# Buck_3_3V_line_07.net
KiCad netlist of a schematic drawn in Altium Designer
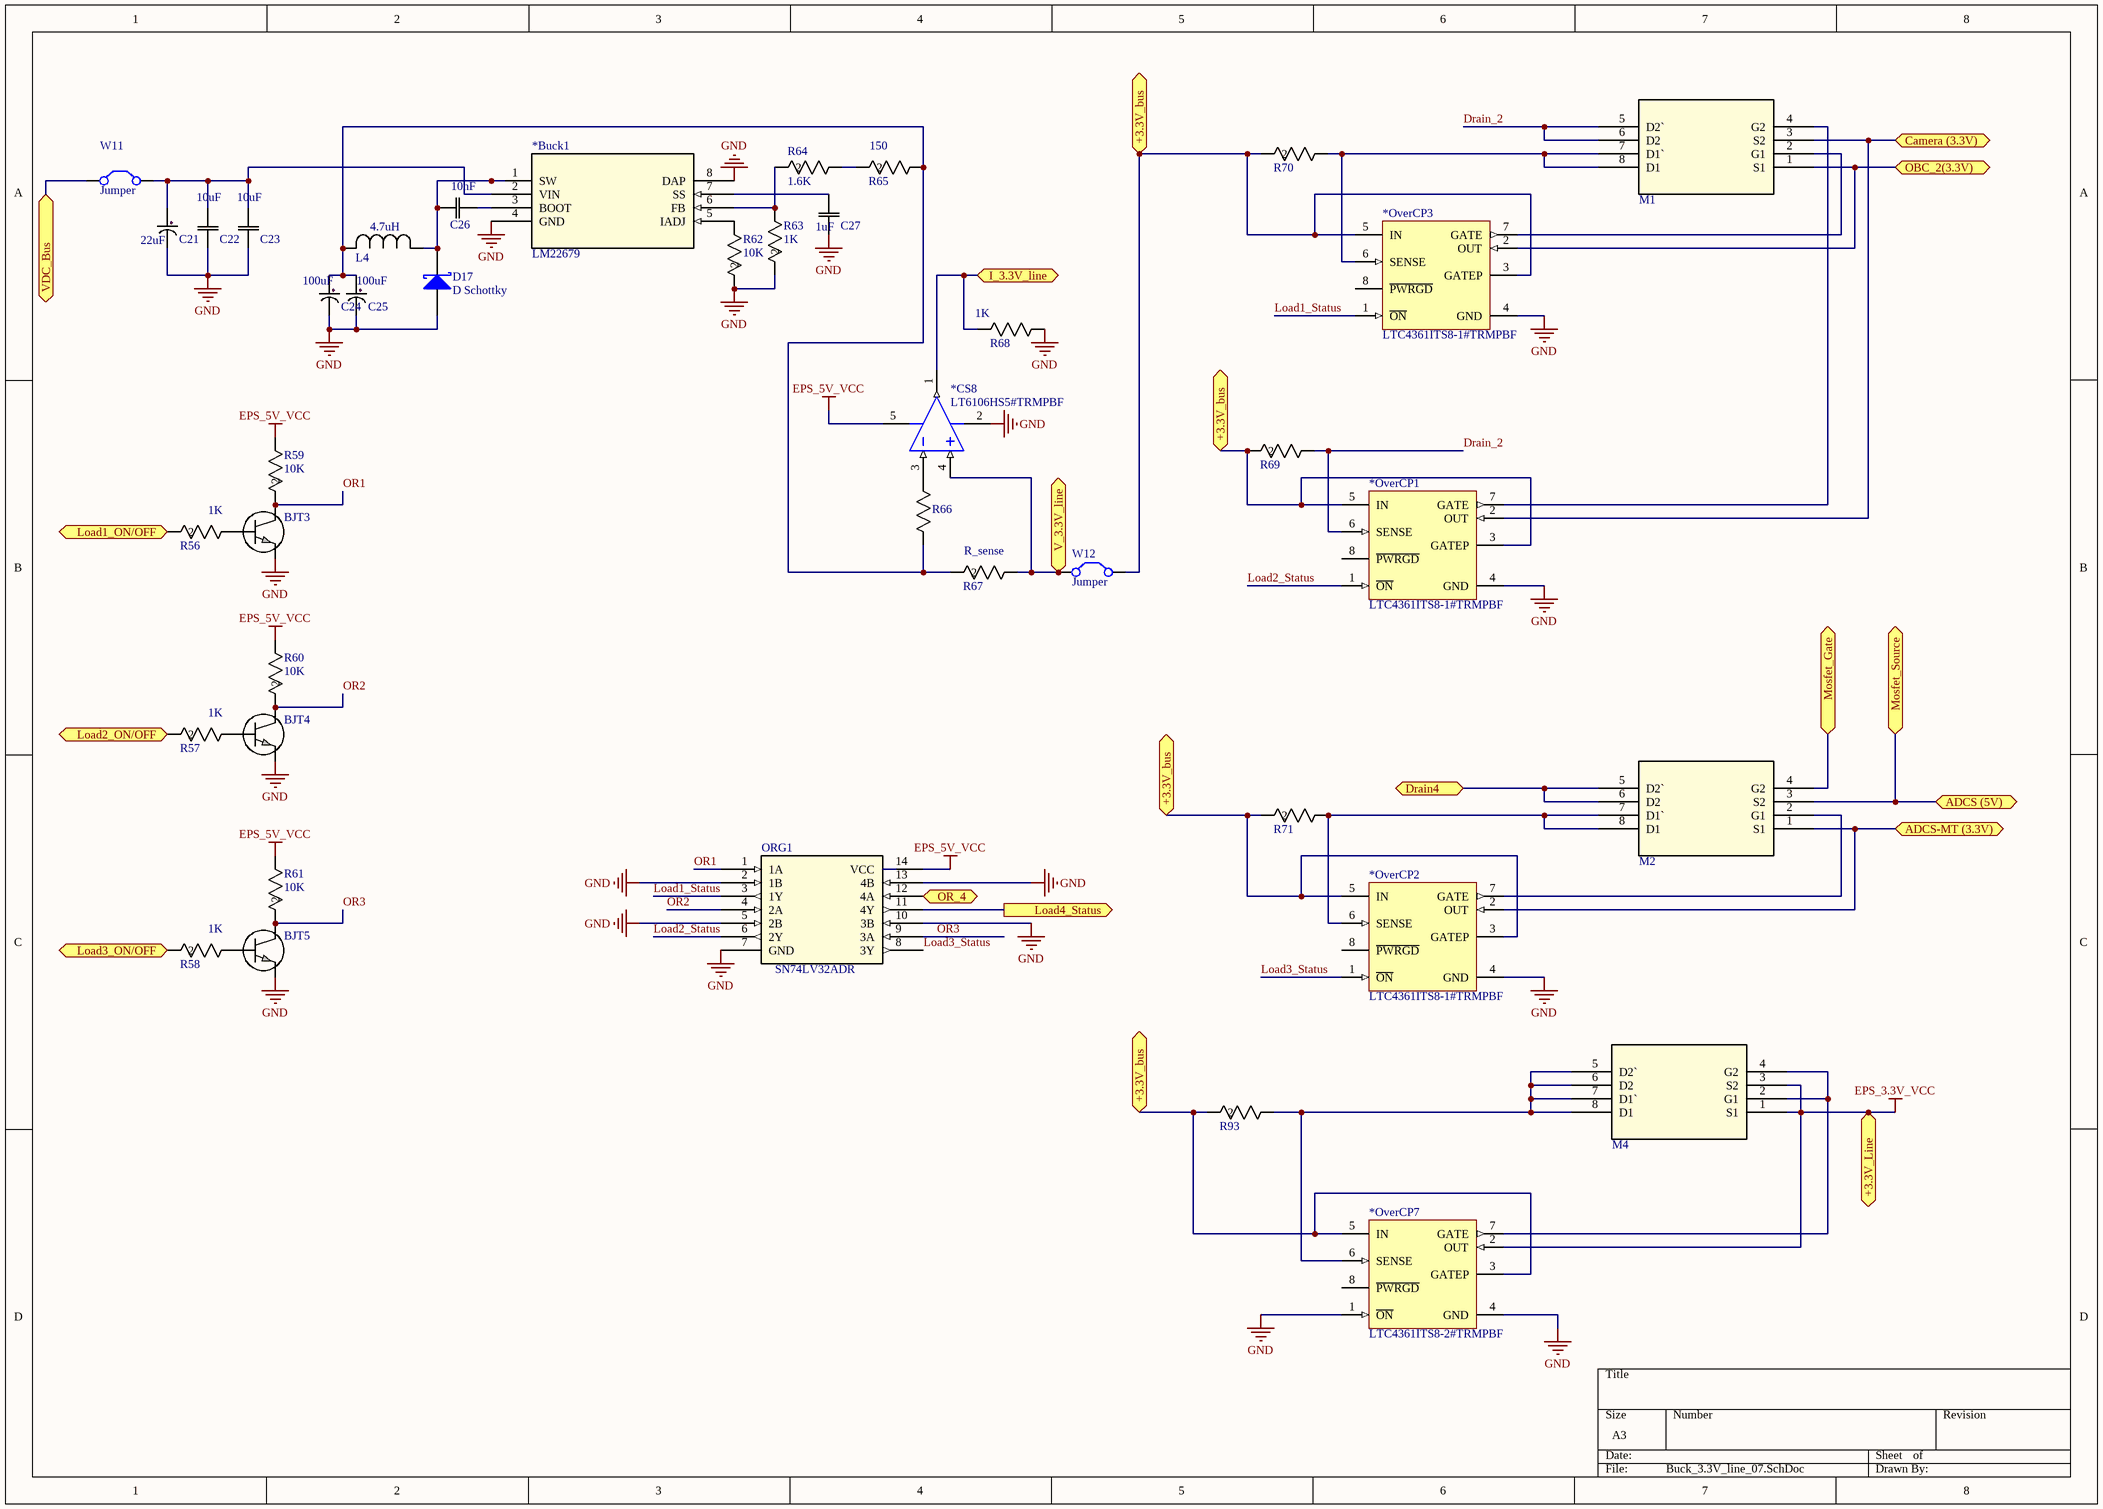
[diagram p0: Buck_3.3V_line_07.SchDoc]

(export (version "E")
  (design (tool "Eeschema 10.0.6"))
  (components
    (comp (ref "*Buck1")
      (value "LM22679")
      (footprint "TJ7A-M")
      (description "step down converter")
      (fields
        (field (name "MANUFACTURER_PART_NUMBER") "lm22679tj-adjnopb")
        (field (name "COPYRIGHT") "Copyright (C) 2015 Accelerated Designs. All rights reserved")
      )
      (libsource (lib "EPS_lib") (part "LM22679"))
    )
    (comp (ref "*CS8")
      (value "LT6106HS5#TRMPBF")
      (footprint "LT-S5-5-TSOT-23_N")
      (fields
        (field (name "LINEAR TECHNOLOGY PART NUMBER") "LT6106")
        (field (name "MANUFACTURER") "Linear Technology")
      )
      (libsource (lib "Linear Technology Operational Amplifiers (LT2000-LT6000)") (part "LT6106HS5#TRMPBF"))
    )
    (comp (ref "*OverCP1")
      (value "LTC4361ITS8-1#TRMPBF")
      (footprint "LT-TS8-8-TSOT-23_V")
      (fields (field (name "MANUFACTURER") "Linear Technology"))
      (libsource (lib "trial05") (part "LTC4361ITS8-1#TRMPBF"))
    )
    (comp (ref "*OverCP2")
      (value "LTC4361ITS8-1#TRMPBF")
      (footprint "LT-TS8-8-TSOT-23_V")
      (fields (field (name "MANUFACTURER") "Linear Technology"))
      (libsource (lib "trial05") (part "LTC4361ITS8-1#TRMPBF"))
    )
    (comp (ref "*OverCP3")
      (value "LTC4361ITS8-1#TRMPBF")
      (footprint "LT-TS8-8-TSOT-23_V")
      (fields (field (name "MANUFACTURER") "Linear Technology"))
      (libsource (lib "trial05") (part "LTC4361ITS8-1#TRMPBF"))
    )
    (comp (ref "*OverCP7")
      (value "LTC4361ITS8-2#TRMPBF")
      (footprint "LT-TS8-8-TSOT-23_V")
      (fields
        (field (name "MANUFACTURER") "Linear Technology")
        (field (name "PARTNUMBER") "LTC4361ITS8-1#TRMPBF")
      )
      (libsource (lib "trial05") (part "LTC4361ITS8-1#TRMPBF"))
    )
    (comp (ref "BJT3")
      (value "MMBT2222A")
      (footprint "SOT-23A_L")
      (description "BJT")
      (fields
        (field (name "MANUFACTURER_PART_NUMBER") "2STF1360")
        (field (name "DIGIKEYPARTNUMBER") "497-5211-2-ND")
        (field (name "COPYRIGHT") "Copyright (C) 2015 Accelerated Designs. All rights reserved")
      )
      (libsource (lib "PCDU_Library") (part "2STF1360"))
    )
    (comp (ref "BJT4")
      (value "MMBT2222A")
      (footprint "SOT-23A_L")
      (description "BJT")
      (fields
        (field (name "MANUFACTURER_PART_NUMBER") "2STF1360")
        (field (name "DIGIKEYPARTNUMBER") "497-5211-2-ND")
        (field (name "COPYRIGHT") "Copyright (C) 2015 Accelerated Designs. All rights reserved")
      )
      (libsource (lib "PCDU_Library") (part "2STF1360"))
    )
    (comp (ref "BJT5")
      (value "MMBT2222A")
      (footprint "SOT-23A_L")
      (description "BJT")
      (fields
        (field (name "MANUFACTURER_PART_NUMBER") "2STF1360")
        (field (name "DIGIKEYPARTNUMBER") "497-5211-2-ND")
        (field (name "COPYRIGHT") "Copyright (C) 2015 Accelerated Designs. All rights reserved")
      )
      (libsource (lib "PCDU_Library") (part "2STF1360"))
    )
    (comp (ref "C21")
      (value "22uF")
      (footprint "TAJB")
      (description "Tantalum Capacitor, 22uF")
      (fields
        (field (name "MANUFACTURER_PART_NUMBER") "TAJB226M010RNJ")
        (field (name "COPYRIGHT") "Copyright (C) 2015 Accelerated Designs. All rights reserved")
      )
      (libsource (lib "PCDU_Library") (part "TAJB226M010RNJ"))
    )
    (comp (ref "C22")
      (value "10uF")
      (footprint "PcbLib1:RC0805N")
      (description "Ceramic Capacitor 10uF")
      (fields
        (field (name "DIGIKEYPARTNUMBER") "399-4925-2-ND")
        (field (name "MANUFACTURER_PART_NUMBER") "C0805C106K8PACTU")
        (field (name "COPYRIGHT") "Copyright (C) 2015 Accelerated Designs. All rights reserved")
      )
      (libsource (lib "PCDU_Library") (part "C0805C106K8PACTU"))
    )
    (comp (ref "C23")
      (value "10uF")
      (footprint "PcbLib1:RC0805N")
      (description "Ceramic Capacitor 10uF")
      (fields
        (field (name "DIGIKEYPARTNUMBER") "399-4925-2-ND")
        (field (name "MANUFACTURER_PART_NUMBER") "C0805C106K8PACTU")
        (field (name "COPYRIGHT") "Copyright (C) 2015 Accelerated Designs. All rights reserved")
      )
      (libsource (lib "PCDU_Library") (part "C0805C106K8PACTU"))
    )
    (comp (ref "C24")
      (value "100uF")
      (footprint "TAJB")
      (description "Tantalum Capacitor. 100uF")
      (fields
        (field (name "MANUFACTURER_PART_NUMBER") "TAJB226M010RNJ")
        (field (name "COPYRIGHT") "Copyright (C) 2015 Accelerated Designs. All rights reserved")
      )
      (libsource (lib "PCDU_Library") (part "TAJB226M010RNJ"))
    )
    (comp (ref "C25")
      (value "100uF")
      (footprint "TAJB")
      (description "Tantalum Capacitor, 100uF")
      (fields
        (field (name "MANUFACTURER_PART_NUMBER") "TAJB226M010RNJ")
        (field (name "COPYRIGHT") "Copyright (C) 2015 Accelerated Designs. All rights reserved")
      )
      (libsource (lib "PCDU_Library") (part "TAJB226M010RNJ"))
    )
    (comp (ref "C26")
      (value "10nF")
      (footprint "RC0805N")
      (description "Ceramic Capacitor 10nF")
      (fields
        (field (name "MANUFACTURER_PART_NUMBER") "GRM155R71H103KA88D")
        (field (name "COPYRIGHT") "Copyright (C) 2015 Accelerated Designs. All rights reserved")
      )
      (libsource (lib "PCDU_Library") (part "GRM155R71H103KA8"))
    )
    (comp (ref "C27")
      (value "1uF")
      (footprint "PcbLib1:RC0805N")
      (description "Ceramic Capacitor 1uF")
      (fields
        (field (name "MANUFACTURER_PART_NUMBER") "GRM188R61C105KA93D")
        (field (name "COPYRIGHT") "Copyright (C) 2015 Accelerated Designs. All rights reserved")
      )
      (libsource (lib "PCDU_Library") (part "GRM188R61C105KA9"))
    )
    (comp (ref "D17")
      (value "D Schottky")
      (footprint "SMB")
      (description "Schottky Diode, 3A")
      (fields (field (name "PUBLISHER") "Altium Limited"))
      (libsource (lib "PCDU_Library") (part "D Schottky"))
    )
    (comp (ref "L4")
      (value "4.7uH")
      (footprint "IND_SPM6530")
      (description "Inductor, 4.7uH")
      (fields
        (field (name "MANUFACTURER_PART_NUMBER") "SPM6530T-4R7M")
        (field (name "COPYRIGHT") "Copyright (C) 2015 Accelerated Designs. All rights reserved")
      )
      (libsource (lib "PCDU_Library") (part "SPM6530T-4R7M"))
    )
    (comp (ref "M1")
      (value "IRF7329TRPBF")
      (footprint "SO8_L")
      (description "P-MOSFET, DUAL PCh -12V 9.2A")
      (fields
        (field (name "MANUFACTURER") "Infineon / IR")
        (field (name "MOUSER PART NO") "942-IRF7329TRPBF")
      )
      (libsource (lib "PCDU_Library") (part "IRF7329TRPBF"))
    )
    (comp (ref "M2")
      (value "IRF7329TRPBF")
      (footprint "SO8_L")
      (description "P-MOSFET, DUAL PCh -12V 9.2A")
      (fields
        (field (name "MANUFACTURER") "Infineon / IR")
        (field (name "MOUSER PART NO") "942-IRF7329TRPBF")
      )
      (libsource (lib "PCDU_Library") (part "IRF7329TRPBF"))
    )
    (comp (ref "M4")
      (value "IRF7329TRPBF")
      (footprint "SO8_L")
      (description "P-MOSFET, DUAL PCh -12V 9.2A")
      (fields
        (field (name "MANUFACTURER") "Infineon / IR")
        (field (name "MOUSER PART NO") "942-IRF7329TRPBF")
      )
      (libsource (lib "PCDU_Library") (part "IRF7329TRPBF"))
    )
    (comp (ref "ORG1")
      (value "SN74LV32ADR")
      (footprint "D14-M")
      (description "OR GATE, 4 Channels")
      (fields
        (field (name "MANUFACTURER") "Texas Instruments")
        (field (name "GENERIC_PART_NUMBER") "SN74LV32A")
        (field (name "COPYRIGHT") "Copyright (C) 2015 Accelerated Designs. All rights reserved")
      )
      (libsource (lib "PCDU_Library") (part "SN74LV32ADR"))
    )
    (comp (ref "R56")
      (value "1K")
      (footprint "RC0805N")
      (description "Thick Film Resistors, 1k ohm")
      (fields
        (field (name "DIGIKEYPARTNUMBER") "311-4.70KCRTR-ND")
        (field (name "MANUFACTURER_PART_NUMBER") "RC0805FR-074K7L")
        (field (name "COPYRIGHT") "Copyright (C) 2015 Accelerated Designs. All rights reserved")
      )
      (libsource (lib "PCDU_Library") (part "RC0805FR"))
    )
    (comp (ref "R57")
      (value "1K")
      (footprint "RC0805N")
      (description "Thick Film Resistors, 1k ohm")
      (fields
        (field (name "DIGIKEYPARTNUMBER") "311-4.70KCRTR-ND")
        (field (name "MANUFACTURER_PART_NUMBER") "RC0805FR-074K7L")
        (field (name "COPYRIGHT") "Copyright (C) 2015 Accelerated Designs. All rights reserved")
      )
      (libsource (lib "PCDU_Library") (part "RC0805FR"))
    )
    (comp (ref "R58")
      (value "1K")
      (footprint "RC0805N")
      (description "Thick Film Resistors, 1k ohm")
      (fields
        (field (name "DIGIKEYPARTNUMBER") "311-4.70KCRTR-ND")
        (field (name "MANUFACTURER_PART_NUMBER") "RC0805FR-074K7L")
        (field (name "COPYRIGHT") "Copyright (C) 2015 Accelerated Designs. All rights reserved")
      )
      (libsource (lib "PCDU_Library") (part "RC0805FR"))
    )
    (comp (ref "R59")
      (value "10K")
      (footprint "PcbLib1:RC0805N")
      (description "Thick Film Resistors, 10k ohm")
      (fields
        (field (name "DIGIKEYPARTNUMBER") "311-4.70KCRTR-ND")
        (field (name "MANUFACTURER_PART_NUMBER") "RC0805FR-074K7L")
        (field (name "COPYRIGHT") "Copyright (C) 2015 Accelerated Designs. All rights reserved")
      )
      (libsource (lib "PCDU_Library") (part "RC0805FR"))
    )
    (comp (ref "R60")
      (value "10K")
      (footprint "PcbLib1:RC0805N")
      (description "Thick Film Resistors, 10k ohm")
      (fields
        (field (name "DIGIKEYPARTNUMBER") "311-4.70KCRTR-ND")
        (field (name "MANUFACTURER_PART_NUMBER") "RC0805FR-074K7L")
        (field (name "COPYRIGHT") "Copyright (C) 2015 Accelerated Designs. All rights reserved")
      )
      (libsource (lib "PCDU_Library") (part "RC0805FR"))
    )
    (comp (ref "R61")
      (value "10K")
      (footprint "PcbLib1:RC0805N")
      (description "Thick Film Resistors, 10k ohm")
      (fields
        (field (name "DIGIKEYPARTNUMBER") "311-4.70KCRTR-ND")
        (field (name "MANUFACTURER_PART_NUMBER") "RC0805FR-074K7L")
        (field (name "COPYRIGHT") "Copyright (C) 2015 Accelerated Designs. All rights reserved")
      )
      (libsource (lib "PCDU_Library") (part "RC0805FR"))
    )
    (comp (ref "R62")
      (value "10K")
      (footprint "RC0805N")
      (description "Thick Film Resistors 10k ohm")
      (fields
        (field (name "DIGIKEYPARTNUMBER") "311-4.70KCRTR-ND")
        (field (name "MANUFACTURER_PART_NUMBER") "RC0805FR-074K7L")
        (field (name "COPYRIGHT") "Copyright (C) 2015 Accelerated Designs. All rights reserved")
      )
      (libsource (lib "PCDU_Library") (part "RC0805FR"))
    )
    (comp (ref "R63")
      (value "1K")
      (footprint "RC0805N")
      (description "Thick Film Resistors, 1k ohm")
      (fields
        (field (name "DIGIKEYPARTNUMBER") "311-4.70KCRTR-ND")
        (field (name "MANUFACTURER_PART_NUMBER") "RC0805FR-074K7L")
        (field (name "COPYRIGHT") "Copyright (C) 2015 Accelerated Designs. All rights reserved")
      )
      (libsource (lib "PCDU_Library") (part "RC0805FR"))
    )
    (comp (ref "R64")
      (value "1.6K")
      (footprint "RC0805N")
      (description "Thick Film Resistors, 1.6kohm")
      (fields
        (field (name "DIGIKEYPARTNUMBER") "311-4.70KCRTR-ND")
        (field (name "MANUFACTURER_PART_NUMBER") "RC0805FR-074K7L")
        (field (name "COPYRIGHT") "Copyright (C) 2015 Accelerated Designs. All rights reserved")
      )
      (libsource (lib "PCDU_Library") (part "RC0805FR"))
    )
    (comp (ref "R65")
      (value "150")
      (footprint "RC0805N")
      (description "Thick Film Resistors, 150 ohm")
      (fields
        (field (name "DIGIKEYPARTNUMBER") "311-4.70KCRTR-ND")
        (field (name "MANUFACTURER_PART_NUMBER") "RC0805FR-074K7L")
        (field (name "COPYRIGHT") "Copyright (C) 2015 Accelerated Designs. All rights reserved")
      )
      (libsource (lib "PCDU_Library") (part "RC0805FR"))
    )
    (comp (ref "R66")
      (value "1K")
      (footprint "RC0805N")
      (description "Thick Film Resistors 0805")
      (fields
        (field (name "DIGIKEYPARTNUMBER") "311-4.70KCRTR-ND")
        (field (name "MANUFACTURER_PART_NUMBER") "RC0805FR-074K7L")
        (field (name "COPYRIGHT") "Copyright (C) 2015 Accelerated Designs. All rights reserved")
      )
      (libsource (lib "Schlib1") (part "RC0805FR"))
    )
    (comp (ref "R67")
      (value "R_sense")
      (footprint "RC0805N")
      (description "Sense Resistor 100m ohm 0805")
      (fields
        (field (name "DIGIKEYPARTNUMBER") "311-.10STR-ND")
        (field (name "MANUFACTURER_PART_NUMBER") "RL0805FR-070R1L")
        (field (name "COPYRIGHT") "Copyright (C) 2015 Accelerated Designs. All rights reserved")
      )
      (libsource (lib "Schlib1") (part "RL0805FR-070R1L"))
    )
    (comp (ref "R68")
      (value "1K")
      (footprint "RC0805N")
      (description "Thick Film Resistors 0805")
      (fields
        (field (name "DIGIKEYPARTNUMBER") "311-4.70KCRTR-ND")
        (field (name "MANUFACTURER_PART_NUMBER") "RC0805FR-074K7L")
        (field (name "COPYRIGHT") "Copyright (C) 2015 Accelerated Designs. All rights reserved")
      )
      (libsource (lib "Schlib1") (part "RC0805FR"))
    )
    (comp (ref "R69")
      (value "RL0805FR-070R1L")
      (footprint "RC0805N")
      (description "Sense Resistor 100m ohm 0805")
      (fields
        (field (name "DIGIKEYPARTNUMBER") "311-.10STR-ND")
        (field (name "TOLERANCE") "Â±1%")
        (field (name "COPYRIGHT") "Copyright (C) 2015 Accelerated Designs. All rights reserved")
      )
      (libsource (lib "Schlib1") (part "RL0805FR-070R1L"))
    )
    (comp (ref "R70")
      (value "RL0805FR-070R1L")
      (footprint "RC0805N")
      (description "Sense Resistor 100m ohm 0805")
      (fields
        (field (name "DIGIKEYPARTNUMBER") "311-.10STR-ND")
        (field (name "TOLERANCE") "Â±1%")
        (field (name "COPYRIGHT") "Copyright (C) 2015 Accelerated Designs. All rights reserved")
      )
      (libsource (lib "Schlib1") (part "RL0805FR-070R1L"))
    )
    (comp (ref "R71")
      (value "RL0805FR-070R1L")
      (footprint "RC0805N")
      (description "Sense Resistor 100m ohm 0805")
      (fields
        (field (name "DIGIKEYPARTNUMBER") "311-.10STR-ND")
        (field (name "TOLERANCE") "Â±1%")
        (field (name "COPYRIGHT") "Copyright (C) 2015 Accelerated Designs. All rights reserved")
      )
      (libsource (lib "Schlib1") (part "RL0805FR-070R1L"))
    )
    (comp (ref "R93")
      (value "RL0805FR-070R1L")
      (footprint "RC0805N")
      (description "Sense Resistor 100m ohm 0805")
      (fields
        (field (name "DIGIKEYPARTNUMBER") "311-.10STR-ND")
        (field (name "TOLERANCE") "Â±1%")
        (field (name "COPYRIGHT") "Copyright (C) 2015 Accelerated Designs. All rights reserved")
      )
      (libsource (lib "Schlib1") (part "RL0805FR-070R1L"))
    )
    (comp (ref "W11")
      (value "Jumper")
      (footprint "PcbLib1:RAD-0.1")
      (description "Jumper Wire")
      (fields (field (name "PUBLISHER") "Altium Limited"))
      (libsource (lib "EPS_lib") (part "Jumper"))
    )
    (comp (ref "W12")
      (value "Jumper")
      (footprint "PcbLib1:RAD-0.1")
      (description "Jumper Wire")
      (fields (field (name "PUBLISHER") "Altium Limited"))
      (libsource (lib "Miscellaneous Devices") (part "Jumper"))
    )
  )
  (nets
    (net (code "1") (name "/+3.3V_bus") (class "Default")
      (node (ref "*OverCP1") (pin "3") (pinfunction "GATEP_3") (pintype "passive"))
      (node (ref "*OverCP1") (pin "5") (pinfunction "IN_5") (pintype "power_in"))
      (node (ref "*OverCP2") (pin "3") (pinfunction "GATEP_3") (pintype "passive"))
      (node (ref "*OverCP2") (pin "5") (pinfunction "IN_5") (pintype "power_in"))
      (node (ref "*OverCP3") (pin "3") (pinfunction "GATEP_3") (pintype "passive"))
      (node (ref "*OverCP3") (pin "5") (pinfunction "IN_5") (pintype "power_in"))
      (node (ref "*OverCP7") (pin "3") (pinfunction "GATEP_3") (pintype "passive"))
      (node (ref "*OverCP7") (pin "5") (pinfunction "IN_5") (pintype "power_in"))
      (node (ref "R69") (pin "2") (pinfunction "2_2") (pintype "passive"))
      (node (ref "R70") (pin "2") (pinfunction "2_2") (pintype "passive"))
      (node (ref "R71") (pin "2") (pinfunction "2_2") (pintype "passive"))
      (node (ref "R93") (pin "2") (pinfunction "2_2") (pintype "passive"))
      (node (ref "W12") (pin "2") (pinfunction "C2_2") (pintype "passive"))
    )
    (net (code "2") (name "/ADCS (5V)") (class "Default")
      (node (ref "M2") (pin "3") (pinfunction "S2_3") (pintype "passive"))
    )
    (net (code "3") (name "/ADCS-MT (3.3V)") (class "Default")
      (node (ref "*OverCP2") (pin "2") (pinfunction "OUT_2") (pintype "input"))
      (node (ref "M2") (pin "1") (pinfunction "S1_1") (pintype "passive"))
    )
    (net (code "4") (name "/Camera (3.3V)") (class "Default")
      (node (ref "*OverCP1") (pin "2") (pinfunction "OUT_2") (pintype "input"))
      (node (ref "M1") (pin "3") (pinfunction "S2_3") (pintype "passive"))
    )
    (net (code "5") (name "/Drain4") (class "Default")
      (node (ref "M2") (pin "5") (pinfunction "D2`_5") (pintype "passive"))
      (node (ref "M2") (pin "6") (pinfunction "D2_6") (pintype "passive"))
    )
    (net (code "6") (name "/Drain_2") (class "Default")
      (node (ref "*OverCP1") (pin "6") (pinfunction "SENSE_6") (pintype "input"))
      (node (ref "M1") (pin "5") (pinfunction "D2`_5") (pintype "passive"))
      (node (ref "M1") (pin "6") (pinfunction "D2_6") (pintype "passive"))
      (node (ref "R69") (pin "1") (pinfunction "1_1") (pintype "passive"))
    )
    (net (code "7") (name "/I_3.3V_line") (class "Default")
      (node (ref "*CS8") (pin "1") (pinfunction "OUT_1") (pintype "output"))
      (node (ref "R68") (pin "1") (pinfunction "1_1") (pintype "passive"))
    )
    (net (code "8") (name "/Load1_ON{slash}OFF") (class "Default")
      (node (ref "R56") (pin "2") (pinfunction "2_2") (pintype "passive"))
    )
    (net (code "9") (name "/Load1_Status") (class "Default")
      (node (ref "*OverCP3") (pin "1") (pinfunction "~{ON}_1") (pintype "input"))
      (node (ref "ORG1") (pin "3") (pinfunction "1Y_3") (pintype "output"))
    )
    (net (code "10") (name "/Load2_ON{slash}OFF") (class "Default")
      (node (ref "R57") (pin "2") (pinfunction "2_2") (pintype "passive"))
    )
    (net (code "11") (name "/Load2_Status") (class "Default")
      (node (ref "*OverCP1") (pin "1") (pinfunction "~{ON}_1") (pintype "input"))
      (node (ref "ORG1") (pin "6") (pinfunction "2Y_6") (pintype "output"))
    )
    (net (code "12") (name "/Load3_ON{slash}OFF") (class "Default")
      (node (ref "R58") (pin "2") (pinfunction "2_2") (pintype "passive"))
    )
    (net (code "13") (name "/Load3_Status") (class "Default")
      (node (ref "*OverCP2") (pin "1") (pinfunction "~{ON}_1") (pintype "input"))
      (node (ref "ORG1") (pin "8") (pinfunction "3Y_8") (pintype "output"))
    )
    (net (code "14") (name "/Load4_Status") (class "Default")
      (node (ref "ORG1") (pin "11") (pinfunction "4Y_11") (pintype "output"))
    )
    (net (code "15") (name "/Mosfet_Gate") (class "Default")
      (node (ref "M2") (pin "4") (pinfunction "G2_4") (pintype "passive"))
    )
    (net (code "16") (name "/OBC_2(3.3V)") (class "Default")
      (node (ref "*OverCP3") (pin "2") (pinfunction "OUT_2") (pintype "input"))
      (node (ref "M1") (pin "1") (pinfunction "S1_1") (pintype "passive"))
    )
    (net (code "17") (name "/OR1") (class "Default")
      (node (ref "BJT3") (pin "2") (pinfunction "C_2") (pintype "passive"))
      (node (ref "ORG1") (pin "1") (pinfunction "1A_1") (pintype "input"))
      (node (ref "R59") (pin "2") (pinfunction "2_2") (pintype "passive"))
    )
    (net (code "18") (name "/OR2") (class "Default")
      (node (ref "BJT4") (pin "2") (pinfunction "C_2") (pintype "passive"))
      (node (ref "ORG1") (pin "4") (pinfunction "2A_4") (pintype "input"))
      (node (ref "R60") (pin "2") (pinfunction "2_2") (pintype "passive"))
    )
    (net (code "19") (name "/OR3") (class "Default")
      (node (ref "BJT5") (pin "2") (pinfunction "C_2") (pintype "passive"))
      (node (ref "ORG1") (pin "9") (pinfunction "3A_9") (pintype "input"))
      (node (ref "R61") (pin "2") (pinfunction "2_2") (pintype "passive"))
    )
    (net (code "20") (name "/OR_4") (class "Default")
      (node (ref "ORG1") (pin "12") (pinfunction "4A_12") (pintype "input"))
    )
    (net (code "21") (name "/VDC_Bus") (class "Default")
      (node (ref "W11") (pin "1") (pinfunction "C1_1") (pintype "passive"))
    )
    (net (code "22") (name "/V_3.3V_line") (class "Default")
      (node (ref "*CS8") (pin "4") (pinfunction "+IN_4") (pintype "input"))
      (node (ref "R67") (pin "1") (pinfunction "1_1") (pintype "passive"))
      (node (ref "W12") (pin "1") (pinfunction "C1_1") (pintype "passive"))
    )
    (net (code "23") (name "EPS_3.3V_VCC") (class "Default")
      (node (ref "*OverCP7") (pin "2") (pinfunction "OUT_2") (pintype "input"))
      (node (ref "M4") (pin "1") (pinfunction "S1_1") (pintype "passive"))
      (node (ref "M4") (pin "3") (pinfunction "S2_3") (pintype "passive"))
    )
    (net (code "24") (name "EPS_5V_VCC") (class "Default")
      (node (ref "*CS8") (pin "5") (pinfunction "V+_5") (pintype "power_in"))
      (node (ref "ORG1") (pin "14") (pinfunction "VCC_14") (pintype "power_in"))
      (node (ref "R59") (pin "1") (pinfunction "1_1") (pintype "passive"))
      (node (ref "R60") (pin "1") (pinfunction "1_1") (pintype "passive"))
      (node (ref "R61") (pin "1") (pinfunction "1_1") (pintype "passive"))
    )
    (net (code "25") (name "GND") (class "Default")
      (node (ref "*Buck1") (pin "4") (pinfunction "GND_4") (pintype "power_in"))
      (node (ref "*Buck1") (pin "8") (pinfunction "DAP_8") (pintype "power_in"))
      (node (ref "*CS8") (pin "2") (pinfunction "V-_2") (pintype "power_in"))
      (node (ref "*OverCP1") (pin "4") (pinfunction "GND_4") (pintype "power_in"))
      (node (ref "*OverCP2") (pin "4") (pinfunction "GND_4") (pintype "power_in"))
      (node (ref "*OverCP3") (pin "4") (pinfunction "GND_4") (pintype "power_in"))
      (node (ref "*OverCP7") (pin "1") (pinfunction "~{ON}_1") (pintype "input"))
      (node (ref "*OverCP7") (pin "4") (pinfunction "GND_4") (pintype "power_in"))
      (node (ref "BJT3") (pin "3") (pinfunction "E_3") (pintype "passive"))
      (node (ref "BJT4") (pin "3") (pinfunction "E_3") (pintype "passive"))
      (node (ref "BJT5") (pin "3") (pinfunction "E_3") (pintype "passive"))
      (node (ref "C21") (pin "2") (pinfunction "2_2") (pintype "passive"))
      (node (ref "C22") (pin "1") (pinfunction "1_1") (pintype "passive"))
      (node (ref "C23") (pin "1") (pinfunction "1_1") (pintype "passive"))
      (node (ref "C24") (pin "2") (pinfunction "2_2") (pintype "passive"))
      (node (ref "C25") (pin "2") (pinfunction "2_2") (pintype "passive"))
      (node (ref "C27") (pin "1") (pinfunction "1_1") (pintype "passive"))
      (node (ref "D17") (pin "1") (pinfunction "A_1") (pintype "passive"))
      (node (ref "ORG1") (pin "10") (pinfunction "3B_10") (pintype "input"))
      (node (ref "ORG1") (pin "13") (pinfunction "4B_13") (pintype "input"))
      (node (ref "ORG1") (pin "2") (pinfunction "1B_2") (pintype "input"))
      (node (ref "ORG1") (pin "5") (pinfunction "2B_5") (pintype "input"))
      (node (ref "ORG1") (pin "7") (pinfunction "GND_7") (pintype "power_in"))
      (node (ref "R62") (pin "2") (pinfunction "2_2") (pintype "passive"))
      (node (ref "R63") (pin "2") (pinfunction "2_2") (pintype "passive"))
      (node (ref "R68") (pin "2") (pinfunction "2_2") (pintype "passive"))
    )
    (net (code "26") (name "Net-(*Buck1-BOOT)") (class "Default")
      (node (ref "*Buck1") (pin "3") (pinfunction "BOOT_3") (pintype "passive"))
      (node (ref "C26") (pin "1") (pinfunction "1_1") (pintype "passive"))
    )
    (net (code "27") (name "Net-(*Buck1-FB)") (class "Default")
      (node (ref "*Buck1") (pin "6") (pinfunction "FB_6") (pintype "input"))
      (node (ref "R63") (pin "1") (pinfunction "1_1") (pintype "passive"))
      (node (ref "R64") (pin "2") (pinfunction "2_2") (pintype "passive"))
    )
    (net (code "28") (name "Net-(*Buck1-IADJ)") (class "Default")
      (node (ref "*Buck1") (pin "5") (pinfunction "IADJ_5") (pintype "input"))
      (node (ref "R62") (pin "1") (pinfunction "1_1") (pintype "passive"))
    )
    (net (code "29") (name "Net-(*Buck1-SS)") (class "Default")
      (node (ref "*Buck1") (pin "7") (pinfunction "SS_7") (pintype "input"))
      (node (ref "C27") (pin "2") (pinfunction "2_2") (pintype "passive"))
    )
    (net (code "30") (name "Net-(*Buck1-SW)") (class "Default")
      (node (ref "*Buck1") (pin "1") (pinfunction "SW_1") (pintype "power_in"))
      (node (ref "C26") (pin "2") (pinfunction "2_2") (pintype "passive"))
      (node (ref "D17") (pin "2") (pinfunction "K_2") (pintype "passive"))
      (node (ref "L4") (pin "1") (pinfunction "1_1") (pintype "passive"))
    )
    (net (code "31") (name "Net-(*Buck1-VIN)") (class "Default")
      (node (ref "*Buck1") (pin "2") (pinfunction "VIN_2") (pintype "power_in"))
      (node (ref "C21") (pin "1") (pinfunction "1_1") (pintype "passive"))
      (node (ref "C22") (pin "2") (pinfunction "2_2") (pintype "passive"))
      (node (ref "C23") (pin "2") (pinfunction "2_2") (pintype "passive"))
      (node (ref "W11") (pin "2") (pinfunction "C2_2") (pintype "passive"))
    )
    (net (code "32") (name "Net-(*CS8--IN)") (class "Default")
      (node (ref "*CS8") (pin "3") (pinfunction "-IN_3") (pintype "input"))
      (node (ref "R66") (pin "1") (pinfunction "1_1") (pintype "passive"))
    )
    (net (code "33") (name "Net-(*OverCP1-GATE)") (class "Default")
      (node (ref "*OverCP1") (pin "7") (pinfunction "GATE_7") (pintype "output"))
      (node (ref "M1") (pin "4") (pinfunction "G2_4") (pintype "passive"))
    )
    (net (code "34") (name "Net-(*OverCP2-GATE)") (class "Default")
      (node (ref "*OverCP2") (pin "7") (pinfunction "GATE_7") (pintype "output"))
      (node (ref "M2") (pin "2") (pinfunction "G1_2") (pintype "passive"))
    )
    (net (code "35") (name "Net-(*OverCP2-SENSE)") (class "Default")
      (node (ref "*OverCP2") (pin "6") (pinfunction "SENSE_6") (pintype "input"))
      (node (ref "M2") (pin "7") (pinfunction "D1`_7") (pintype "passive"))
      (node (ref "M2") (pin "8") (pinfunction "D1_8") (pintype "passive"))
      (node (ref "R71") (pin "1") (pinfunction "1_1") (pintype "passive"))
    )
    (net (code "36") (name "Net-(*OverCP3-GATE)") (class "Default")
      (node (ref "*OverCP3") (pin "7") (pinfunction "GATE_7") (pintype "output"))
      (node (ref "M1") (pin "2") (pinfunction "G1_2") (pintype "passive"))
    )
    (net (code "37") (name "Net-(*OverCP3-SENSE)") (class "Default")
      (node (ref "*OverCP3") (pin "6") (pinfunction "SENSE_6") (pintype "input"))
      (node (ref "M1") (pin "7") (pinfunction "D1`_7") (pintype "passive"))
      (node (ref "M1") (pin "8") (pinfunction "D1_8") (pintype "passive"))
      (node (ref "R70") (pin "1") (pinfunction "1_1") (pintype "passive"))
    )
    (net (code "38") (name "Net-(*OverCP7-GATE)") (class "Default")
      (node (ref "*OverCP7") (pin "7") (pinfunction "GATE_7") (pintype "output"))
      (node (ref "M4") (pin "2") (pinfunction "G1_2") (pintype "passive"))
      (node (ref "M4") (pin "4") (pinfunction "G2_4") (pintype "passive"))
    )
    (net (code "39") (name "Net-(*OverCP7-SENSE)") (class "Default")
      (node (ref "*OverCP7") (pin "6") (pinfunction "SENSE_6") (pintype "input"))
      (node (ref "M4") (pin "5") (pinfunction "D2`_5") (pintype "passive"))
      (node (ref "M4") (pin "6") (pinfunction "D2_6") (pintype "passive"))
      (node (ref "M4") (pin "7") (pinfunction "D1`_7") (pintype "passive"))
      (node (ref "M4") (pin "8") (pinfunction "D1_8") (pintype "passive"))
      (node (ref "R93") (pin "1") (pinfunction "1_1") (pintype "passive"))
    )
    (net (code "40") (name "Net-(BJT3-B)") (class "Default")
      (node (ref "BJT3") (pin "1") (pinfunction "B_1") (pintype "passive"))
      (node (ref "R56") (pin "1") (pinfunction "1_1") (pintype "passive"))
    )
    (net (code "41") (name "Net-(BJT4-B)") (class "Default")
      (node (ref "BJT4") (pin "1") (pinfunction "B_1") (pintype "passive"))
      (node (ref "R57") (pin "1") (pinfunction "1_1") (pintype "passive"))
    )
    (net (code "42") (name "Net-(BJT5-B)") (class "Default")
      (node (ref "BJT5") (pin "1") (pinfunction "B_1") (pintype "passive"))
      (node (ref "R58") (pin "1") (pinfunction "1_1") (pintype "passive"))
    )
    (net (code "43") (name "Net-(C24-Pad1)") (class "Default")
      (node (ref "C24") (pin "1") (pinfunction "1_1") (pintype "passive"))
      (node (ref "C25") (pin "1") (pinfunction "1_1") (pintype "passive"))
      (node (ref "L4") (pin "2") (pinfunction "2_2") (pintype "passive"))
      (node (ref "R65") (pin "1") (pinfunction "1_1") (pintype "passive"))
      (node (ref "R66") (pin "2") (pinfunction "2_2") (pintype "passive"))
      (node (ref "R67") (pin "2") (pinfunction "2_2") (pintype "passive"))
    )
    (net (code "44") (name "Net-(R64-Pad1)") (class "Default")
      (node (ref "R64") (pin "1") (pinfunction "1_1") (pintype "passive"))
      (node (ref "R65") (pin "2") (pinfunction "2_2") (pintype "passive"))
    )
    (net (code "45") (name "unconnected-(*OverCP1-~{PWRGD}-Pad8)") (class "Default")
      (node (ref "*OverCP1") (pin "8") (pinfunction "~{PWRGD}_8") (pintype "tri_state"))
    )
    (net (code "46") (name "unconnected-(*OverCP2-~{PWRGD}-Pad8)") (class "Default")
      (node (ref "*OverCP2") (pin "8") (pinfunction "~{PWRGD}_8") (pintype "tri_state"))
    )
    (net (code "47") (name "unconnected-(*OverCP3-~{PWRGD}-Pad8)") (class "Default")
      (node (ref "*OverCP3") (pin "8") (pinfunction "~{PWRGD}_8") (pintype "tri_state"))
    )
    (net (code "48") (name "unconnected-(*OverCP7-~{PWRGD}-Pad8)") (class "Default")
      (node (ref "*OverCP7") (pin "8") (pinfunction "~{PWRGD}_8") (pintype "tri_state"))
    )
  )
)
